# Urukul_FPGA_LVDS.net
KiCad netlist of a schematic drawn in Altium Designer
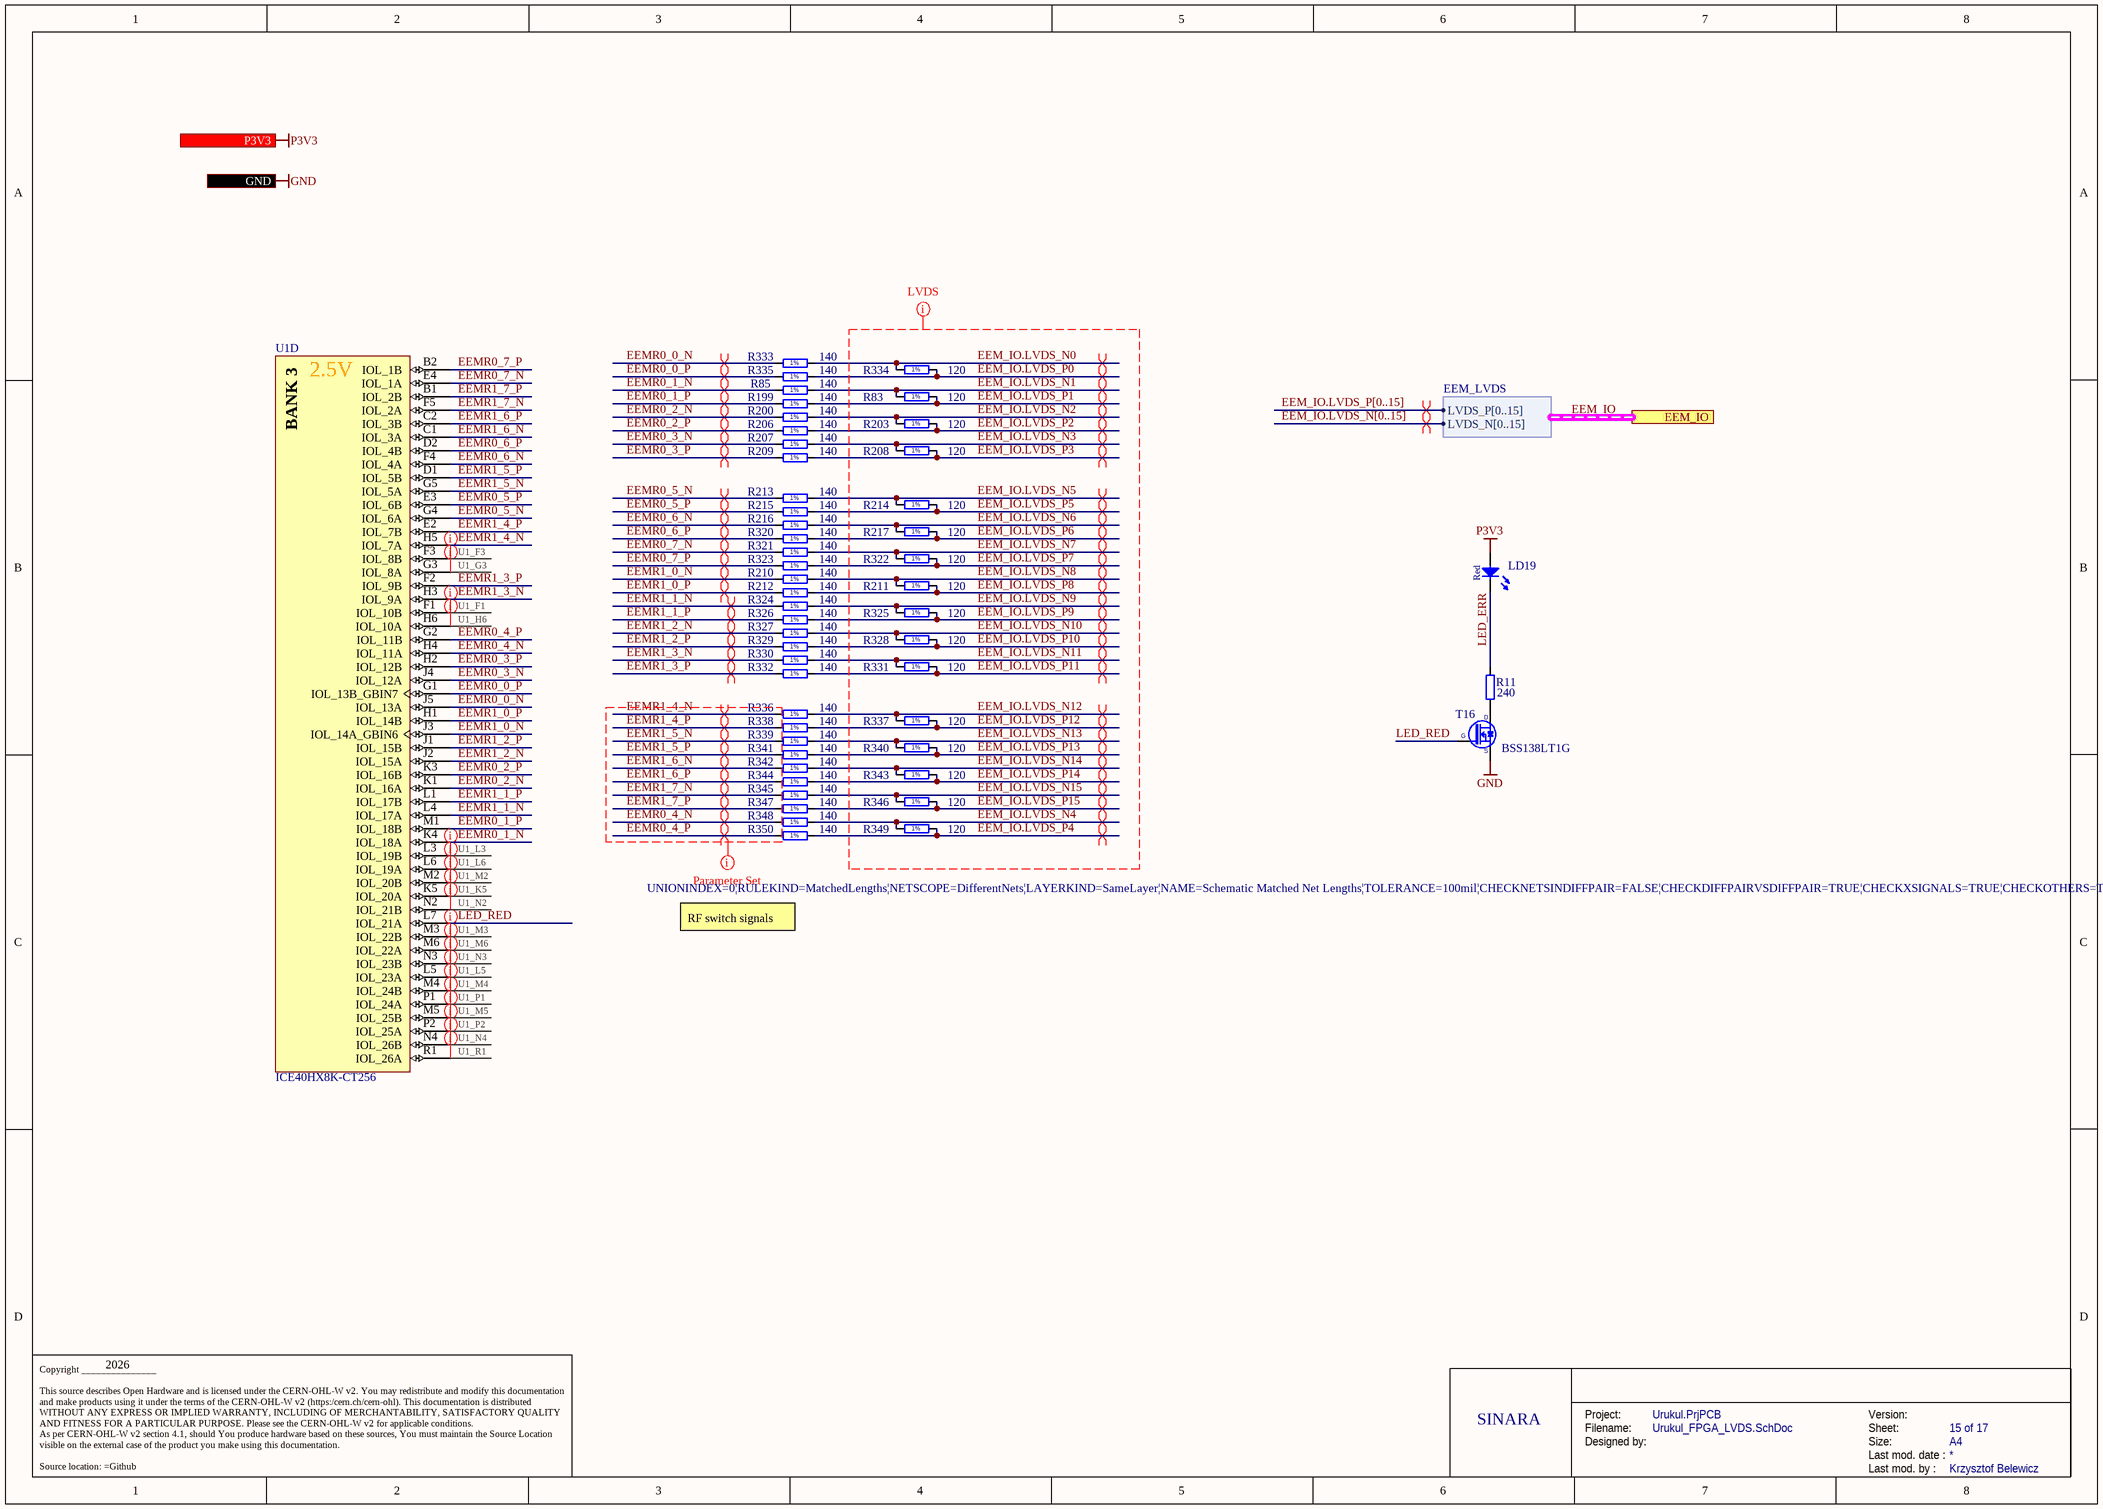
[diagram p0: Urukul_FPGA_LVDS.SchDoc]

(export (version "E")
  (design (tool "Eeschema 10.0.6"))
  (components
    (comp (ref "LD19")
      (value "Red")
      (footprint "LED_AVAGO_HSMC-C120")
      (description "LED Red 1C 2A")
      (fields
        (field (name "PART NUMBER") "LED_AVAGO_HSMC-C120")
        (field (name "MANUFACTURER") "AVAGO TECHNOLOGIES")
        (field (name "AUTHOR") "CERN DEM JMW")
      )
      (libsource (lib "ICs And Semiconductors") (part "LED Red 1C 2A"))
    )
    (comp (ref "R11")
      (value "240")
      (footprint "RESC1005X40N")
      (description "Resistor - 1%")
      (fields
        (field (name "PART NUMBER") "R0402_240R_1%_0.0625W_100PPM")
        (field (name "POWER") "0.0625W")
        (field (name "AUTHOR") "CERN DEM JLC")
      )
      (libsource (lib "Resistors") (part "Resistor - 1%"))
    )
    (comp (ref "R83")
      (value "120")
      (footprint "RESC1005X40N")
      (description "Resistor - 1%")
      (fields
        (field (name "PART NUMBER") "R0402_120R_1%_0.0625W_100PPM")
        (field (name "POWER") "0.0625W")
        (field (name "AUTHOR") "CERN DEM JLC")
      )
      (libsource (lib "") (part "Resistor - 1%_1"))
    )
    (comp (ref "R85")
      (value "140")
      (footprint "RESC0603X28N")
      (description "Resistor - 1%")
      (fields
        (field (name "PART NUMBER") "R0201_140R_1%_0.05W_200PPM")
        (field (name "POWER") "0.05W")
        (field (name "AUTHOR") "CERN DEM MR")
      )
      (libsource (lib "") (part "Resistor - 1%_1"))
    )
    (comp (ref "R199")
      (value "140")
      (footprint "RESC0603X28N")
      (description "Resistor - 1%")
      (fields
        (field (name "PART NUMBER") "R0201_140R_1%_0.05W_200PPM")
        (field (name "POWER") "0.05W")
        (field (name "AUTHOR") "CERN DEM MR")
      )
      (libsource (lib "") (part "Resistor - 1%_1"))
    )
    (comp (ref "R200")
      (value "140")
      (footprint "RESC0603X28N")
      (description "Resistor - 1%")
      (fields
        (field (name "PART NUMBER") "R0201_140R_1%_0.05W_200PPM")
        (field (name "POWER") "0.05W")
        (field (name "AUTHOR") "CERN DEM MR")
      )
      (libsource (lib "") (part "Resistor - 1%_1"))
    )
    (comp (ref "R203")
      (value "120")
      (footprint "RESC1005X40N")
      (description "Resistor - 1%")
      (fields
        (field (name "PART NUMBER") "R0402_120R_1%_0.0625W_100PPM")
        (field (name "POWER") "0.0625W")
        (field (name "AUTHOR") "CERN DEM JLC")
      )
      (libsource (lib "") (part "Resistor - 1%_1"))
    )
    (comp (ref "R206")
      (value "140")
      (footprint "RESC0603X28N")
      (description "Resistor - 1%")
      (fields
        (field (name "PART NUMBER") "R0201_140R_1%_0.05W_200PPM")
        (field (name "POWER") "0.05W")
        (field (name "AUTHOR") "CERN DEM MR")
      )
      (libsource (lib "") (part "Resistor - 1%_1"))
    )
    (comp (ref "R207")
      (value "140")
      (footprint "RESC0603X28N")
      (description "Resistor - 1%")
      (fields
        (field (name "PART NUMBER") "R0201_140R_1%_0.05W_200PPM")
        (field (name "POWER") "0.05W")
        (field (name "AUTHOR") "CERN DEM MR")
      )
      (libsource (lib "") (part "Resistor - 1%_1"))
    )
    (comp (ref "R208")
      (value "120")
      (footprint "RESC1005X40N")
      (description "Resistor - 1%")
      (fields
        (field (name "PART NUMBER") "R0402_120R_1%_0.0625W_100PPM")
        (field (name "POWER") "0.0625W")
        (field (name "AUTHOR") "CERN DEM JLC")
      )
      (libsource (lib "") (part "Resistor - 1%_1"))
    )
    (comp (ref "R209")
      (value "140")
      (footprint "RESC0603X28N")
      (description "Resistor - 1%")
      (fields
        (field (name "PART NUMBER") "R0201_140R_1%_0.05W_200PPM")
        (field (name "POWER") "0.05W")
        (field (name "AUTHOR") "CERN DEM MR")
      )
      (libsource (lib "") (part "Resistor - 1%_1"))
    )
    (comp (ref "R210")
      (value "140")
      (footprint "RESC0603X28N")
      (description "Resistor - 1%")
      (fields
        (field (name "PART NUMBER") "R0201_140R_1%_0.05W_200PPM")
        (field (name "POWER") "0.05W")
        (field (name "AUTHOR") "CERN DEM MR")
      )
      (libsource (lib "") (part "Resistor - 1%_1"))
    )
    (comp (ref "R211")
      (value "120")
      (footprint "RESC1005X40N")
      (description "Resistor - 1%")
      (fields
        (field (name "PART NUMBER") "R0402_120R_1%_0.0625W_100PPM")
        (field (name "POWER") "0.0625W")
        (field (name "AUTHOR") "CERN DEM JLC")
      )
      (libsource (lib "") (part "Resistor - 1%_1"))
    )
    (comp (ref "R212")
      (value "140")
      (footprint "RESC0603X28N")
      (description "Resistor - 1%")
      (fields
        (field (name "PART NUMBER") "R0201_140R_1%_0.05W_200PPM")
        (field (name "POWER") "0.05W")
        (field (name "AUTHOR") "CERN DEM MR")
      )
      (libsource (lib "") (part "Resistor - 1%_1"))
    )
    (comp (ref "R213")
      (value "140")
      (footprint "RESC0603X28N")
      (description "Resistor - 1%")
      (fields
        (field (name "PART NUMBER") "R0201_140R_1%_0.05W_200PPM")
        (field (name "POWER") "0.05W")
        (field (name "AUTHOR") "CERN DEM MR")
      )
      (libsource (lib "") (part "Resistor - 1%_1"))
    )
    (comp (ref "R214")
      (value "120")
      (footprint "RESC1005X40N")
      (description "Resistor - 1%")
      (fields
        (field (name "PART NUMBER") "R0402_120R_1%_0.0625W_100PPM")
        (field (name "POWER") "0.0625W")
        (field (name "AUTHOR") "CERN DEM JLC")
      )
      (libsource (lib "") (part "Resistor - 1%_1"))
    )
    (comp (ref "R215")
      (value "140")
      (footprint "RESC0603X28N")
      (description "Resistor - 1%")
      (fields
        (field (name "PART NUMBER") "R0201_140R_1%_0.05W_200PPM")
        (field (name "POWER") "0.05W")
        (field (name "AUTHOR") "CERN DEM MR")
      )
      (libsource (lib "") (part "Resistor - 1%_1"))
    )
    (comp (ref "R216")
      (value "140")
      (footprint "RESC0603X28N")
      (description "Resistor - 1%")
      (fields
        (field (name "PART NUMBER") "R0201_140R_1%_0.05W_200PPM")
        (field (name "POWER") "0.05W")
        (field (name "AUTHOR") "CERN DEM MR")
      )
      (libsource (lib "") (part "Resistor - 1%_1"))
    )
    (comp (ref "R217")
      (value "120")
      (footprint "RESC1005X40N")
      (description "Resistor - 1%")
      (fields
        (field (name "PART NUMBER") "R0402_120R_1%_0.0625W_100PPM")
        (field (name "POWER") "0.0625W")
        (field (name "AUTHOR") "CERN DEM JLC")
      )
      (libsource (lib "") (part "Resistor - 1%_1"))
    )
    (comp (ref "R320")
      (value "140")
      (footprint "RESC0603X28N")
      (description "Resistor - 1%")
      (fields
        (field (name "PART NUMBER") "R0201_140R_1%_0.05W_200PPM")
        (field (name "POWER") "0.05W")
        (field (name "AUTHOR") "CERN DEM MR")
      )
      (libsource (lib "") (part "Resistor - 1%_1"))
    )
    (comp (ref "R321")
      (value "140")
      (footprint "RESC0603X28N")
      (description "Resistor - 1%")
      (fields
        (field (name "PART NUMBER") "R0201_140R_1%_0.05W_200PPM")
        (field (name "POWER") "0.05W")
        (field (name "AUTHOR") "CERN DEM MR")
      )
      (libsource (lib "") (part "Resistor - 1%_1"))
    )
    (comp (ref "R322")
      (value "120")
      (footprint "RESC1005X40N")
      (description "Resistor - 1%")
      (fields
        (field (name "PART NUMBER") "R0402_120R_1%_0.0625W_100PPM")
        (field (name "POWER") "0.0625W")
        (field (name "AUTHOR") "CERN DEM JLC")
      )
      (libsource (lib "") (part "Resistor - 1%_1"))
    )
    (comp (ref "R323")
      (value "140")
      (footprint "RESC0603X28N")
      (description "Resistor - 1%")
      (fields
        (field (name "PART NUMBER") "R0201_140R_1%_0.05W_200PPM")
        (field (name "POWER") "0.05W")
        (field (name "AUTHOR") "CERN DEM MR")
      )
      (libsource (lib "") (part "Resistor - 1%_1"))
    )
    (comp (ref "R324")
      (value "140")
      (footprint "RESC0603X28N")
      (description "Resistor - 1%")
      (fields
        (field (name "PART NUMBER") "R0201_140R_1%_0.05W_200PPM")
        (field (name "POWER") "0.05W")
        (field (name "AUTHOR") "CERN DEM MR")
      )
      (libsource (lib "") (part "Resistor - 1%_1"))
    )
    (comp (ref "R325")
      (value "120")
      (footprint "RESC1005X40N")
      (description "Resistor - 1%")
      (fields
        (field (name "PART NUMBER") "R0402_120R_1%_0.0625W_100PPM")
        (field (name "POWER") "0.0625W")
        (field (name "AUTHOR") "CERN DEM JLC")
      )
      (libsource (lib "") (part "Resistor - 1%_1"))
    )
    (comp (ref "R326")
      (value "140")
      (footprint "RESC0603X28N")
      (description "Resistor - 1%")
      (fields
        (field (name "PART NUMBER") "R0201_140R_1%_0.05W_200PPM")
        (field (name "POWER") "0.05W")
        (field (name "AUTHOR") "CERN DEM MR")
      )
      (libsource (lib "") (part "Resistor - 1%_1"))
    )
    (comp (ref "R327")
      (value "140")
      (footprint "RESC0603X28N")
      (description "Resistor - 1%")
      (fields
        (field (name "PART NUMBER") "R0201_140R_1%_0.05W_200PPM")
        (field (name "POWER") "0.05W")
        (field (name "AUTHOR") "CERN DEM MR")
      )
      (libsource (lib "") (part "Resistor - 1%_1"))
    )
    (comp (ref "R328")
      (value "120")
      (footprint "RESC1005X40N")
      (description "Resistor - 1%")
      (fields
        (field (name "PART NUMBER") "R0402_120R_1%_0.0625W_100PPM")
        (field (name "POWER") "0.0625W")
        (field (name "AUTHOR") "CERN DEM JLC")
      )
      (libsource (lib "") (part "Resistor - 1%_1"))
    )
    (comp (ref "R329")
      (value "140")
      (footprint "RESC0603X28N")
      (description "Resistor - 1%")
      (fields
        (field (name "PART NUMBER") "R0201_140R_1%_0.05W_200PPM")
        (field (name "POWER") "0.05W")
        (field (name "AUTHOR") "CERN DEM MR")
      )
      (libsource (lib "") (part "Resistor - 1%_1"))
    )
    (comp (ref "R330")
      (value "140")
      (footprint "RESC0603X28N")
      (description "Resistor - 1%")
      (fields
        (field (name "PART NUMBER") "R0201_140R_1%_0.05W_200PPM")
        (field (name "POWER") "0.05W")
        (field (name "AUTHOR") "CERN DEM MR")
      )
      (libsource (lib "") (part "Resistor - 1%_1"))
    )
    (comp (ref "R331")
      (value "120")
      (footprint "RESC1005X40N")
      (description "Resistor - 1%")
      (fields
        (field (name "PART NUMBER") "R0402_120R_1%_0.0625W_100PPM")
        (field (name "POWER") "0.0625W")
        (field (name "AUTHOR") "CERN DEM JLC")
      )
      (libsource (lib "") (part "Resistor - 1%_1"))
    )
    (comp (ref "R332")
      (value "140")
      (footprint "RESC0603X28N")
      (description "Resistor - 1%")
      (fields
        (field (name "PART NUMBER") "R0201_140R_1%_0.05W_200PPM")
        (field (name "POWER") "0.05W")
        (field (name "AUTHOR") "CERN DEM MR")
      )
      (libsource (lib "") (part "Resistor - 1%_1"))
    )
    (comp (ref "R333")
      (value "140")
      (footprint "RESC0603X28N")
      (description "Resistor - 1%")
      (fields
        (field (name "PART NUMBER") "R0201_140R_1%_0.05W_200PPM")
        (field (name "POWER") "0.05W")
        (field (name "AUTHOR") "CERN DEM MR")
      )
      (libsource (lib "") (part "Resistor - 1%_1"))
    )
    (comp (ref "R334")
      (value "120")
      (footprint "RESC1005X40N")
      (description "Resistor - 1%")
      (fields
        (field (name "PART NUMBER") "R0402_120R_1%_0.0625W_100PPM")
        (field (name "POWER") "0.0625W")
        (field (name "AUTHOR") "CERN DEM JLC")
      )
      (libsource (lib "") (part "Resistor - 1%_1"))
    )
    (comp (ref "R335")
      (value "140")
      (footprint "RESC0603X28N")
      (description "Resistor - 1%")
      (fields
        (field (name "PART NUMBER") "R0201_140R_1%_0.05W_200PPM")
        (field (name "POWER") "0.05W")
        (field (name "AUTHOR") "CERN DEM MR")
      )
      (libsource (lib "") (part "Resistor - 1%_1"))
    )
    (comp (ref "R336")
      (value "140")
      (footprint "RESC0603X28N")
      (description "Resistor - 1%")
      (fields
        (field (name "PART NUMBER") "R0201_140R_1%_0.05W_200PPM")
        (field (name "POWER") "0.05W")
        (field (name "AUTHOR") "CERN DEM MR")
      )
      (libsource (lib "") (part "Resistor - 1%_1"))
    )
    (comp (ref "R337")
      (value "120")
      (footprint "RESC1005X40N")
      (description "Resistor - 1%")
      (fields
        (field (name "PART NUMBER") "R0402_120R_1%_0.0625W_100PPM")
        (field (name "POWER") "0.0625W")
        (field (name "AUTHOR") "CERN DEM JLC")
      )
      (libsource (lib "") (part "Resistor - 1%_1"))
    )
    (comp (ref "R338")
      (value "140")
      (footprint "RESC0603X28N")
      (description "Resistor - 1%")
      (fields
        (field (name "PART NUMBER") "R0201_140R_1%_0.05W_200PPM")
        (field (name "POWER") "0.05W")
        (field (name "AUTHOR") "CERN DEM MR")
      )
      (libsource (lib "") (part "Resistor - 1%_1"))
    )
    (comp (ref "R339")
      (value "140")
      (footprint "RESC0603X28N")
      (description "Resistor - 1%")
      (fields
        (field (name "PART NUMBER") "R0201_140R_1%_0.05W_200PPM")
        (field (name "POWER") "0.05W")
        (field (name "AUTHOR") "CERN DEM MR")
      )
      (libsource (lib "") (part "Resistor - 1%_1"))
    )
    (comp (ref "R340")
      (value "120")
      (footprint "RESC1005X40N")
      (description "Resistor - 1%")
      (fields
        (field (name "PART NUMBER") "R0402_120R_1%_0.0625W_100PPM")
        (field (name "POWER") "0.0625W")
        (field (name "AUTHOR") "CERN DEM JLC")
      )
      (libsource (lib "") (part "Resistor - 1%_1"))
    )
    (comp (ref "R341")
      (value "140")
      (footprint "RESC0603X28N")
      (description "Resistor - 1%")
      (fields
        (field (name "PART NUMBER") "R0201_140R_1%_0.05W_200PPM")
        (field (name "POWER") "0.05W")
        (field (name "AUTHOR") "CERN DEM MR")
      )
      (libsource (lib "") (part "Resistor - 1%_1"))
    )
    (comp (ref "R342")
      (value "140")
      (footprint "RESC0603X28N")
      (description "Resistor - 1%")
      (fields
        (field (name "PART NUMBER") "R0201_140R_1%_0.05W_200PPM")
        (field (name "POWER") "0.05W")
        (field (name "AUTHOR") "CERN DEM MR")
      )
      (libsource (lib "") (part "Resistor - 1%_1"))
    )
    (comp (ref "R343")
      (value "120")
      (footprint "RESC1005X40N")
      (description "Resistor - 1%")
      (fields
        (field (name "PART NUMBER") "R0402_120R_1%_0.0625W_100PPM")
        (field (name "POWER") "0.0625W")
        (field (name "AUTHOR") "CERN DEM JLC")
      )
      (libsource (lib "") (part "Resistor - 1%_1"))
    )
    (comp (ref "R344")
      (value "140")
      (footprint "RESC0603X28N")
      (description "Resistor - 1%")
      (fields
        (field (name "PART NUMBER") "R0201_140R_1%_0.05W_200PPM")
        (field (name "POWER") "0.05W")
        (field (name "AUTHOR") "CERN DEM MR")
      )
      (libsource (lib "") (part "Resistor - 1%_1"))
    )
    (comp (ref "R345")
      (value "140")
      (footprint "RESC0603X28N")
      (description "Resistor - 1%")
      (fields
        (field (name "PART NUMBER") "R0201_140R_1%_0.05W_200PPM")
        (field (name "POWER") "0.05W")
        (field (name "AUTHOR") "CERN DEM MR")
      )
      (libsource (lib "") (part "Resistor - 1%_1"))
    )
    (comp (ref "R346")
      (value "120")
      (footprint "RESC1005X40N")
      (description "Resistor - 1%")
      (fields
        (field (name "PART NUMBER") "R0402_120R_1%_0.0625W_100PPM")
        (field (name "POWER") "0.0625W")
        (field (name "AUTHOR") "CERN DEM JLC")
      )
      (libsource (lib "") (part "Resistor - 1%_1"))
    )
    (comp (ref "R347")
      (value "140")
      (footprint "RESC0603X28N")
      (description "Resistor - 1%")
      (fields
        (field (name "PART NUMBER") "R0201_140R_1%_0.05W_200PPM")
        (field (name "POWER") "0.05W")
        (field (name "AUTHOR") "CERN DEM MR")
      )
      (libsource (lib "") (part "Resistor - 1%_1"))
    )
    (comp (ref "R348")
      (value "140")
      (footprint "RESC0603X28N")
      (description "Resistor - 1%")
      (fields
        (field (name "PART NUMBER") "R0201_140R_1%_0.05W_200PPM")
        (field (name "POWER") "0.05W")
        (field (name "AUTHOR") "CERN DEM MR")
      )
      (libsource (lib "") (part "Resistor - 1%_1"))
    )
    (comp (ref "R349")
      (value "120")
      (footprint "RESC1005X40N")
      (description "Resistor - 1%")
      (fields
        (field (name "PART NUMBER") "R0402_120R_1%_0.0625W_100PPM")
        (field (name "POWER") "0.0625W")
        (field (name "AUTHOR") "CERN DEM JLC")
      )
      (libsource (lib "") (part "Resistor - 1%_1"))
    )
    (comp (ref "R350")
      (value "140")
      (footprint "RESC0603X28N")
      (description "Resistor - 1%")
      (fields
        (field (name "PART NUMBER") "R0201_140R_1%_0.05W_200PPM")
        (field (name "POWER") "0.05W")
        (field (name "AUTHOR") "CERN DEM MR")
      )
      (libsource (lib "") (part "Resistor - 1%_1"))
    )
    (comp (ref "T16")
      (value "BSS138LT1G")
      (footprint "SOT95P240X110-3N")
      (description "N-CHANNEL MOSFET WITH DIODE")
      (fields (field (name "MANUFACTURER") "ON SEMICONDUCTOR") (field (name "AUTHOR") "CERN DEM JLC"))
      (libsource (lib "ICs And Semiconductors") (part "N-MOSFET-D 1G 2S 3D"))
    )
    (comp (ref "U1")
      (value "ICE40HX8K-CT256")
      (footprint "LATC-caBGA-256")
      (fields (field (name "MANUFACTURER") "Lattice Semiconductor"))
      (libsource (lib "Altium Content Vault") (part "LATC-HX8K-caBGA-256"))
    )
  )
  (nets
    (net (code "2") (name "/EEMR0_0_N") (class "Default")
      (node (ref "R333") (pin "1") (pinfunction "1_1") (pintype "passive"))
      (node (ref "U1") (pin "J5") (pinfunction "IOL_13A_J5") (pintype "bidirectional"))
    )
    (net (code "3") (name "/EEMR0_0_P") (class "Default")
      (node (ref "R335") (pin "1") (pinfunction "1_1") (pintype "passive"))
      (node (ref "U1") (pin "G1") (pinfunction "IOL_13B_GBIN7_G1") (pintype "bidirectional"))
    )
    (net (code "4") (name "/EEMR0_1_N") (class "Default")
      (node (ref "R85") (pin "1") (pinfunction "1_1") (pintype "passive"))
      (node (ref "U1") (pin "K4") (pinfunction "IOL_18A_K4") (pintype "bidirectional"))
    )
    (net (code "5") (name "/EEMR0_1_P") (class "Default")
      (node (ref "R199") (pin "1") (pinfunction "1_1") (pintype "passive"))
      (node (ref "U1") (pin "M1") (pinfunction "IOL_18B_M1") (pintype "bidirectional"))
    )
    (net (code "6") (name "/EEMR0_2_N") (class "Default")
      (node (ref "R200") (pin "1") (pinfunction "1_1") (pintype "passive"))
      (node (ref "U1") (pin "K1") (pinfunction "IOL_16A_K1") (pintype "bidirectional"))
    )
    (net (code "7") (name "/EEMR0_2_P") (class "Default")
      (node (ref "R206") (pin "1") (pinfunction "1_1") (pintype "passive"))
      (node (ref "U1") (pin "K3") (pinfunction "IOL_16B_K3") (pintype "bidirectional"))
    )
    (net (code "8") (name "/EEMR0_3_N") (class "Default")
      (node (ref "R207") (pin "1") (pinfunction "1_1") (pintype "passive"))
      (node (ref "U1") (pin "J4") (pinfunction "IOL_12A_J4") (pintype "bidirectional"))
    )
    (net (code "9") (name "/EEMR0_3_P") (class "Default")
      (node (ref "R209") (pin "1") (pinfunction "1_1") (pintype "passive"))
      (node (ref "U1") (pin "H2") (pinfunction "IOL_12B_H2") (pintype "bidirectional"))
    )
    (net (code "10") (name "/EEMR0_4_N") (class "Default")
      (node (ref "R348") (pin "1") (pinfunction "1_1") (pintype "passive"))
      (node (ref "U1") (pin "H4") (pinfunction "IOL_11A_H4") (pintype "bidirectional"))
    )
    (net (code "11") (name "/EEMR0_4_P") (class "Default")
      (node (ref "R350") (pin "1") (pinfunction "1_1") (pintype "passive"))
      (node (ref "U1") (pin "G2") (pinfunction "IOL_11B_G2") (pintype "bidirectional"))
    )
    (net (code "12") (name "/EEMR0_5_N") (class "Default")
      (node (ref "R213") (pin "1") (pinfunction "1_1") (pintype "passive"))
      (node (ref "U1") (pin "G4") (pinfunction "IOL_6A_G4") (pintype "bidirectional"))
    )
    (net (code "13") (name "/EEMR0_5_P") (class "Default")
      (node (ref "R215") (pin "1") (pinfunction "1_1") (pintype "passive"))
      (node (ref "U1") (pin "E3") (pinfunction "IOL_6B_E3") (pintype "bidirectional"))
    )
    (net (code "14") (name "/EEMR0_6_N") (class "Default")
      (node (ref "R216") (pin "1") (pinfunction "1_1") (pintype "passive"))
      (node (ref "U1") (pin "F4") (pinfunction "IOL_4A_F4") (pintype "bidirectional"))
    )
    (net (code "15") (name "/EEMR0_6_P") (class "Default")
      (node (ref "R320") (pin "1") (pinfunction "1_1") (pintype "passive"))
      (node (ref "U1") (pin "D2") (pinfunction "IOL_4B_D2") (pintype "bidirectional"))
    )
    (net (code "16") (name "/EEMR0_7_N") (class "Default")
      (node (ref "R321") (pin "1") (pinfunction "1_1") (pintype "passive"))
      (node (ref "U1") (pin "E4") (pinfunction "IOL_1A_E4") (pintype "bidirectional"))
    )
    (net (code "17") (name "/EEMR0_7_P") (class "Default")
      (node (ref "R323") (pin "1") (pinfunction "1_1") (pintype "passive"))
      (node (ref "U1") (pin "B2") (pinfunction "IOL_1B_B2") (pintype "bidirectional"))
    )
    (net (code "18") (name "/EEMR1_0_N") (class "Default")
      (node (ref "R210") (pin "1") (pinfunction "1_1") (pintype "passive"))
      (node (ref "U1") (pin "J3") (pinfunction "IOL_14A_GBIN6_J3") (pintype "bidirectional"))
    )
    (net (code "19") (name "/EEMR1_0_P") (class "Default")
      (node (ref "R212") (pin "1") (pinfunction "1_1") (pintype "passive"))
      (node (ref "U1") (pin "H1") (pinfunction "IOL_14B_H1") (pintype "bidirectional"))
    )
    (net (code "20") (name "/EEMR1_1_N") (class "Default")
      (node (ref "R324") (pin "1") (pinfunction "1_1") (pintype "passive"))
      (node (ref "U1") (pin "L4") (pinfunction "IOL_17A_L4") (pintype "bidirectional"))
    )
    (net (code "21") (name "/EEMR1_1_P") (class "Default")
      (node (ref "R326") (pin "1") (pinfunction "1_1") (pintype "passive"))
      (node (ref "U1") (pin "L1") (pinfunction "IOL_17B_L1") (pintype "bidirectional"))
    )
    (net (code "22") (name "/EEMR1_2_N") (class "Default")
      (node (ref "R327") (pin "1") (pinfunction "1_1") (pintype "passive"))
      (node (ref "U1") (pin "J2") (pinfunction "IOL_15A_J2") (pintype "bidirectional"))
    )
    (net (code "23") (name "/EEMR1_2_P") (class "Default")
      (node (ref "R329") (pin "1") (pinfunction "1_1") (pintype "passive"))
      (node (ref "U1") (pin "J1") (pinfunction "IOL_15B_J1") (pintype "bidirectional"))
    )
    (net (code "24") (name "/EEMR1_3_N") (class "Default")
      (node (ref "R330") (pin "1") (pinfunction "1_1") (pintype "passive"))
      (node (ref "U1") (pin "H3") (pinfunction "IOL_9A_H3") (pintype "bidirectional"))
    )
    (net (code "25") (name "/EEMR1_3_P") (class "Default")
      (node (ref "R332") (pin "1") (pinfunction "1_1") (pintype "passive"))
      (node (ref "U1") (pin "F2") (pinfunction "IOL_9B_F2") (pintype "bidirectional"))
    )
    (net (code "26") (name "/EEMR1_4_N") (class "Default")
      (node (ref "R336") (pin "1") (pinfunction "1_1") (pintype "passive"))
      (node (ref "U1") (pin "H5") (pinfunction "IOL_7A_H5") (pintype "bidirectional"))
    )
    (net (code "27") (name "/EEMR1_4_P") (class "Default")
      (node (ref "R338") (pin "1") (pinfunction "1_1") (pintype "passive"))
      (node (ref "U1") (pin "E2") (pinfunction "IOL_7B_E2") (pintype "bidirectional"))
    )
    (net (code "28") (name "/EEMR1_5_N") (class "Default")
      (node (ref "R339") (pin "1") (pinfunction "1_1") (pintype "passive"))
      (node (ref "U1") (pin "G5") (pinfunction "IOL_5A_G5") (pintype "bidirectional"))
    )
    (net (code "29") (name "/EEMR1_5_P") (class "Default")
      (node (ref "R341") (pin "1") (pinfunction "1_1") (pintype "passive"))
      (node (ref "U1") (pin "D1") (pinfunction "IOL_5B_D1") (pintype "bidirectional"))
    )
    (net (code "30") (name "/EEMR1_6_N") (class "Default")
      (node (ref "R342") (pin "1") (pinfunction "1_1") (pintype "passive"))
      (node (ref "U1") (pin "C1") (pinfunction "IOL_3A_C1") (pintype "bidirectional"))
    )
    (net (code "31") (name "/EEMR1_6_P") (class "Default")
      (node (ref "R344") (pin "1") (pinfunction "1_1") (pintype "passive"))
      (node (ref "U1") (pin "C2") (pinfunction "IOL_3B_C2") (pintype "bidirectional"))
    )
    (net (code "32") (name "/EEMR1_7_N") (class "Default")
      (node (ref "R345") (pin "1") (pinfunction "1_1") (pintype "passive"))
      (node (ref "U1") (pin "F5") (pinfunction "IOL_2A_F5") (pintype "bidirectional"))
    )
    (net (code "33") (name "/EEMR1_7_P") (class "Default")
      (node (ref "R347") (pin "1") (pinfunction "1_1") (pintype "passive"))
      (node (ref "U1") (pin "B1") (pinfunction "IOL_2B_B1") (pintype "bidirectional"))
    )
    (net (code "34") (name "/EEM_IO.LVDS_N0") (class "Default")
      (node (ref "R333") (pin "2") (pinfunction "2_2") (pintype "passive"))
      (node (ref "R334") (pin "1") (pinfunction "1_1") (pintype "passive"))
    )
    (net (code "35") (name "/EEM_IO.LVDS_N1") (class "Default")
      (node (ref "R83") (pin "1") (pinfunction "1_1") (pintype "passive"))
      (node (ref "R85") (pin "2") (pinfunction "2_2") (pintype "passive"))
    )
    (net (code "36") (name "/EEM_IO.LVDS_N2") (class "Default")
      (node (ref "R200") (pin "2") (pinfunction "2_2") (pintype "passive"))
      (node (ref "R203") (pin "1") (pinfunction "1_1") (pintype "passive"))
    )
    (net (code "37") (name "/EEM_IO.LVDS_N3") (class "Default")
      (node (ref "R207") (pin "2") (pinfunction "2_2") (pintype "passive"))
      (node (ref "R208") (pin "1") (pinfunction "1_1") (pintype "passive"))
    )
    (net (code "38") (name "/EEM_IO.LVDS_N4") (class "Default")
      (node (ref "R348") (pin "2") (pinfunction "2_2") (pintype "passive"))
      (node (ref "R349") (pin "1") (pinfunction "1_1") (pintype "passive"))
    )
    (net (code "39") (name "/EEM_IO.LVDS_N5") (class "Default")
      (node (ref "R213") (pin "2") (pinfunction "2_2") (pintype "passive"))
      (node (ref "R214") (pin "1") (pinfunction "1_1") (pintype "passive"))
    )
    (net (code "40") (name "/EEM_IO.LVDS_N6") (class "Default")
      (node (ref "R216") (pin "2") (pinfunction "2_2") (pintype "passive"))
      (node (ref "R217") (pin "1") (pinfunction "1_1") (pintype "passive"))
    )
    (net (code "41") (name "/EEM_IO.LVDS_N7") (class "Default")
      (node (ref "R321") (pin "2") (pinfunction "2_2") (pintype "passive"))
      (node (ref "R322") (pin "1") (pinfunction "1_1") (pintype "passive"))
    )
    (net (code "42") (name "/EEM_IO.LVDS_N8") (class "Default")
      (node (ref "R210") (pin "2") (pinfunction "2_2") (pintype "passive"))
      (node (ref "R211") (pin "1") (pinfunction "1_1") (pintype "passive"))
    )
    (net (code "43") (name "/EEM_IO.LVDS_N9") (class "Default")
      (node (ref "R324") (pin "2") (pinfunction "2_2") (pintype "passive"))
      (node (ref "R325") (pin "1") (pinfunction "1_1") (pintype "passive"))
    )
    (net (code "44") (name "/EEM_IO.LVDS_N10") (class "Default")
      (node (ref "R327") (pin "2") (pinfunction "2_2") (pintype "passive"))
      (node (ref "R328") (pin "1") (pinfunction "1_1") (pintype "passive"))
    )
    (net (code "45") (name "/EEM_IO.LVDS_N11") (class "Default")
      (node (ref "R330") (pin "2") (pinfunction "2_2") (pintype "passive"))
      (node (ref "R331") (pin "1") (pinfunction "1_1") (pintype "passive"))
    )
    (net (code "46") (name "/EEM_IO.LVDS_N12") (class "Default")
      (node (ref "R336") (pin "2") (pinfunction "2_2") (pintype "passive"))
      (node (ref "R337") (pin "1") (pinfunction "1_1") (pintype "passive"))
    )
    (net (code "47") (name "/EEM_IO.LVDS_N13") (class "Default")
      (node (ref "R339") (pin "2") (pinfunction "2_2") (pintype "passive"))
      (node (ref "R340") (pin "1") (pinfunction "1_1") (pintype "passive"))
    )
    (net (code "48") (name "/EEM_IO.LVDS_N14") (class "Default")
      (node (ref "R342") (pin "2") (pinfunction "2_2") (pintype "passive"))
      (node (ref "R343") (pin "1") (pinfunction "1_1") (pintype "passive"))
    )
    (net (code "49") (name "/EEM_IO.LVDS_N15") (class "Default")
      (node (ref "R345") (pin "2") (pinfunction "2_2") (pintype "passive"))
      (node (ref "R346") (pin "1") (pinfunction "1_1") (pintype "passive"))
    )
    (net (code "50") (name "/EEM_IO.LVDS_P0") (class "Default")
      (node (ref "R334") (pin "2") (pinfunction "2_2") (pintype "passive"))
      (node (ref "R335") (pin "2") (pinfunction "2_2") (pintype "passive"))
    )
    (net (code "51") (name "/EEM_IO.LVDS_P1") (class "Default")
      (node (ref "R199") (pin "2") (pinfunction "2_2") (pintype "passive"))
      (node (ref "R83") (pin "2") (pinfunction "2_2") (pintype "passive"))
    )
    (net (code "52") (name "/EEM_IO.LVDS_P2") (class "Default")
      (node (ref "R203") (pin "2") (pinfunction "2_2") (pintype "passive"))
      (node (ref "R206") (pin "2") (pinfunction "2_2") (pintype "passive"))
    )
    (net (code "53") (name "/EEM_IO.LVDS_P3") (class "Default")
      (node (ref "R208") (pin "2") (pinfunction "2_2") (pintype "passive"))
      (node (ref "R209") (pin "2") (pinfunction "2_2") (pintype "passive"))
    )
    (net (code "54") (name "/EEM_IO.LVDS_P4") (class "Default")
      (node (ref "R349") (pin "2") (pinfunction "2_2") (pintype "passive"))
      (node (ref "R350") (pin "2") (pinfunction "2_2") (pintype "passive"))
    )
    (net (code "55") (name "/EEM_IO.LVDS_P5") (class "Default")
      (node (ref "R214") (pin "2") (pinfunction "2_2") (pintype "passive"))
      (node (ref "R215") (pin "2") (pinfunction "2_2") (pintype "passive"))
    )
    (net (code "56") (name "/EEM_IO.LVDS_P6") (class "Default")
      (node (ref "R217") (pin "2") (pinfunction "2_2") (pintype "passive"))
      (node (ref "R320") (pin "2") (pinfunction "2_2") (pintype "passive"))
    )
    (net (code "57") (name "/EEM_IO.LVDS_P7") (class "Default")
      (node (ref "R322") (pin "2") (pinfunction "2_2") (pintype "passive"))
      (node (ref "R323") (pin "2") (pinfunction "2_2") (pintype "passive"))
    )
    (net (code "58") (name "/EEM_IO.LVDS_P8") (class "Default")
      (node (ref "R211") (pin "2") (pinfunction "2_2") (pintype "passive"))
      (node (ref "R212") (pin "2") (pinfunction "2_2") (pintype "passive"))
    )
    (net (code "59") (name "/EEM_IO.LVDS_P9") (class "Default")
      (node (ref "R325") (pin "2") (pinfunction "2_2") (pintype "passive"))
      (node (ref "R326") (pin "2") (pinfunction "2_2") (pintype "passive"))
    )
    (net (code "60") (name "/EEM_IO.LVDS_P10") (class "Default")
      (node (ref "R328") (pin "2") (pinfunction "2_2") (pintype "passive"))
      (node (ref "R329") (pin "2") (pinfunction "2_2") (pintype "passive"))
    )
    (net (code "61") (name "/EEM_IO.LVDS_P11") (class "Default")
      (node (ref "R331") (pin "2") (pinfunction "2_2") (pintype "passive"))
      (node (ref "R332") (pin "2") (pinfunction "2_2") (pintype "passive"))
    )
    (net (code "62") (name "/EEM_IO.LVDS_P12") (class "Default")
      (node (ref "R337") (pin "2") (pinfunction "2_2") (pintype "passive"))
      (node (ref "R338") (pin "2") (pinfunction "2_2") (pintype "passive"))
    )
    (net (code "63") (name "/EEM_IO.LVDS_P13") (class "Default")
      (node (ref "R340") (pin "2") (pinfunction "2_2") (pintype "passive"))
      (node (ref "R341") (pin "2") (pinfunction "2_2") (pintype "passive"))
    )
    (net (code "64") (name "/EEM_IO.LVDS_P14") (class "Default")
      (node (ref "R343") (pin "2") (pinfunction "2_2") (pintype "passive"))
      (node (ref "R344") (pin "2") (pinfunction "2_2") (pintype "passive"))
    )
    (net (code "65") (name "/EEM_IO.LVDS_P15") (class "Default")
      (node (ref "R346") (pin "2") (pinfunction "2_2") (pintype "passive"))
      (node (ref "R347") (pin "2") (pinfunction "2_2") (pintype "passive"))
    )
    (net (code "67") (name "/LED_ERR") (class "Default")
      (node (ref "LD19") (pin "1") (pinfunction "C_1") (pintype "passive"))
      (node (ref "R11") (pin "1") (pinfunction "1_1") (pintype "passive"))
    )
    (net (code "68") (name "/LED_RED") (class "Default")
      (node (ref "T16") (pin "1") (pinfunction "G_1") (pintype "passive"))
      (node (ref "U1") (pin "L7") (pinfunction "IOL_21A_L7") (pintype "bidirectional"))
    )
    (net (code "69") (name "/U1_F1") (class "Default")
      (node (ref "U1") (pin "F1") (pinfunction "IOL_10B_F1") (pintype "bidirectional"))
    )
    (net (code "70") (name "/U1_F3") (class "Default")
      (node (ref "U1") (pin "F3") (pinfunction "IOL_8B_F3") (pintype "bidirectional"))
    )
    (net (code "71") (name "/U1_G3") (class "Default")
      (node (ref "U1") (pin "G3") (pinfunction "IOL_8A_G3") (pintype "bidirectional"))
    )
    (net (code "72") (name "/U1_H6") (class "Default")
      (node (ref "U1") (pin "H6") (pinfunction "IOL_10A_H6") (pintype "bidirectional"))
    )
    (net (code "73") (name "/U1_K5") (class "Default")
      (node (ref "U1") (pin "K5") (pinfunction "IOL_20A_K5") (pintype "bidirectional"))
    )
    (net (code "74") (name "/U1_L3") (class "Default")
      (node (ref "U1") (pin "L3") (pinfunction "IOL_19B_L3") (pintype "bidirectional"))
    )
    (net (code "75") (name "/U1_L5") (class "Default")
      (node (ref "U1") (pin "L5") (pinfunction "IOL_23A_L5") (pintype "bidirectional"))
    )
    (net (code "76") (name "/U1_L6") (class "Default")
      (node (ref "U1") (pin "L6") (pinfunction "IOL_19A_L6") (pintype "bidirectional"))
    )
    (net (code "77") (name "/U1_M2") (class "Default")
      (node (ref "U1") (pin "M2") (pinfunction "IOL_20B_M2") (pintype "bidirectional"))
    )
    (net (code "78") (name "/U1_M3") (class "Default")
      (node (ref "U1") (pin "M3") (pinfunction "IOL_22B_M3") (pintype "bidirectional"))
    )
    (net (code "79") (name "/U1_M4") (class "Default")
      (node (ref "U1") (pin "M4") (pinfunction "IOL_24B_M4") (pintype "bidirectional"))
    )
    (net (code "80") (name "/U1_M5") (class "Default")
      (node (ref "U1") (pin "M5") (pinfunction "IOL_25B_M5") (pintype "bidirectional"))
    )
    (net (code "81") (name "/U1_M6") (class "Default")
      (node (ref "U1") (pin "M6") (pinfunction "IOL_22A_M6") (pintype "bidirectional"))
    )
    (net (code "82") (name "/U1_N2") (class "Default")
      (node (ref "U1") (pin "N2") (pinfunction "IOL_21B_N2") (pintype "bidirectional"))
    )
    (net (code "83") (name "/U1_N3") (class "Default")
      (node (ref "U1") (pin "N3") (pinfunction "IOL_23B_N3") (pintype "bidirectional"))
    )
    (net (code "84") (name "/U1_N4") (class "Default")
      (node (ref "U1") (pin "N4") (pinfunction "IOL_26B_N4") (pintype "bidirectional"))
    )
    (net (code "85") (name "/U1_P1") (class "Default")
      (node (ref "U1") (pin "P1") (pinfunction "IOL_24A_P1") (pintype "bidirectional"))
    )
    (net (code "86") (name "/U1_P2") (class "Default")
      (node (ref "U1") (pin "P2") (pinfunction "IOL_25A_P2") (pintype "bidirectional"))
    )
    (net (code "87") (name "/U1_R1") (class "Default")
      (node (ref "U1") (pin "R1") (pinfunction "IOL_26A_R1") (pintype "bidirectional"))
    )
    (net (code "89") (name "GND") (class "Default")
      (node (ref "T16") (pin "2") (pinfunction "S_2") (pintype "passive"))
    )
    (net (code "90") (name "Net-(T16-D)") (class "Default")
      (node (ref "R11") (pin "2") (pinfunction "2_2") (pintype "passive"))
      (node (ref "T16") (pin "3") (pinfunction "D_3") (pintype "passive"))
    )
    (net (code "91") (name "P3V3") (class "Default")
      (node (ref "LD19") (pin "2") (pinfunction "A_2") (pintype "passive"))
    )
  )
)
